# Memory.net
KiCad netlist of a schematic drawn in Altium Designer
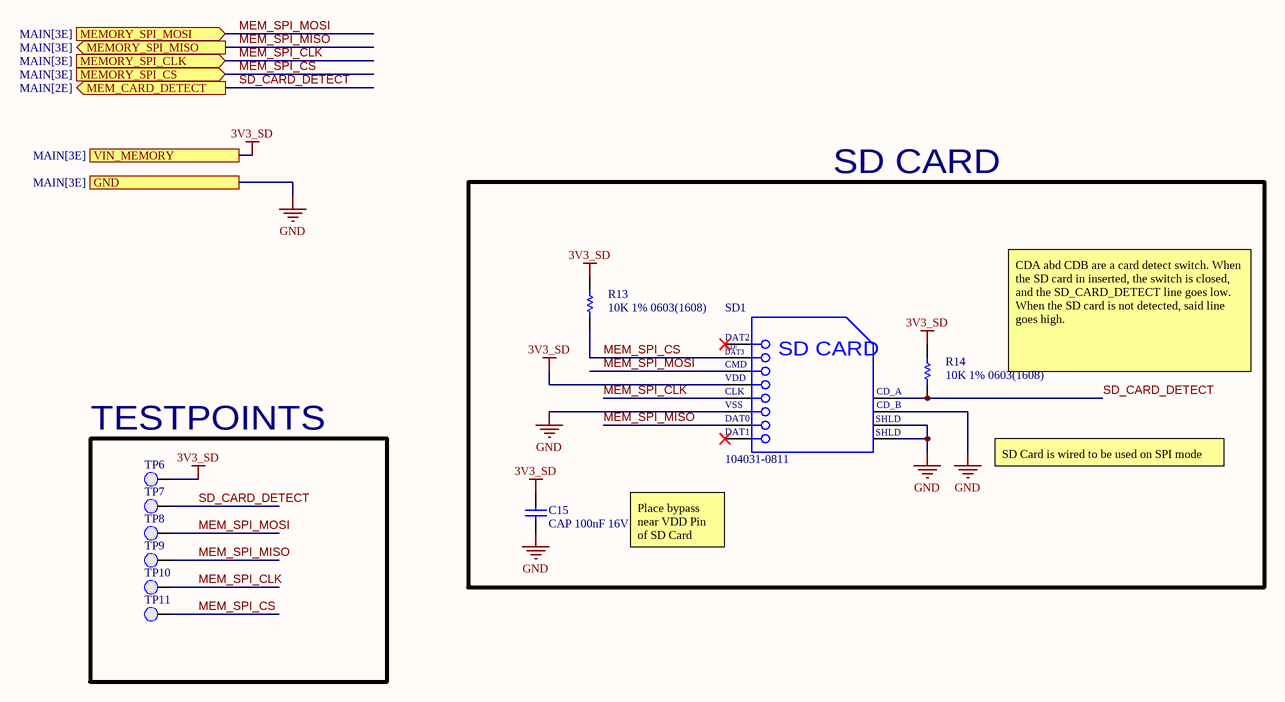
[diagram p0: Memory.SchDoc]

(export (version "E")
  (design (tool "Eeschema 10.0.6"))
  (components
    (comp (ref "C15")
      (value "CAP 100nF 16V 0603(1608)")
      (footprint "CAPC1608X95X40NL15T15")
      (fields (field (name "MANUFACTURER") "Vitramon") (field (name "PART NUMBER") "VJ0603Y104KXJCW1BC"))
      (libsource (lib "Altium Content Vault") (part "CAP"))
    )
    (comp (ref "R13")
      (value "10K 1% 0603(1608)")
      (footprint "RESC1609X55X30LL15T15")
      (description "Chip Resistor, 10 KOhm, +/- 1%, 0.1 W, -55 to 155 degC, 0603 (1608 Metric), RoHS, Tape and Reel")
      (fields (field (name "TOLERANCE") "1%") (field (name "MANUFACTURER") "Panasonic"))
      (libsource (lib "Altium Content Vault") (part "RES-2"))
    )
    (comp (ref "R14")
      (value "10K 1% 0603(1608)")
      (footprint "RESC1609X55X30LL15T15")
      (description "Chip Resistor, 10 KOhm, +/- 1%, 0.1 W, -55 to 155 degC, 0603 (1608 Metric), RoHS, Tape and Reel")
      (fields (field (name "TOLERANCE") "1%") (field (name "MANUFACTURER") "Panasonic"))
      (libsource (lib "Altium Content Vault") (part "RES-2"))
    )
    (comp (ref "SD1")
      (value "104031-0811")
      (footprint "MOLX-104031-0811_V")
      (description "Micro SD Card, RA, -25 to 85 degC, 8-Pin SMD, RoHS, Tape and Reel")
      (fields (field (name "MANUFACTURER") "Molex"))
      (libsource (lib "Altium Content Vault") (part "CN-SD-8-2SW-2S"))
    )
    (comp (ref "TP6")
      (value "0.1\" Pad")
      (footprint "PCBComponent")
      (libsource (lib "Schematics") (part "0.1{dblquote} Pad-A.4"))
    )
    (comp (ref "TP7")
      (value "0.1\" Pad")
      (footprint "PCBComponent")
      (libsource (lib "Schematics") (part "0.1{dblquote} Pad-A.4"))
    )
    (comp (ref "TP8")
      (value "0.1\" Pad")
      (footprint "PCBComponent")
      (libsource (lib "Schematics") (part "0.1{dblquote} Pad-A.4"))
    )
    (comp (ref "TP9")
      (value "0.1\" Pad")
      (footprint "PCBComponent")
      (libsource (lib "Schematics") (part "0.1{dblquote} Pad-A.4"))
    )
    (comp (ref "TP10")
      (value "0.1\" Pad")
      (footprint "PCBComponent")
      (libsource (lib "Schematics") (part "0.1{dblquote} Pad-A.4"))
    )
    (comp (ref "TP11")
      (value "0.1\" Pad")
      (footprint "PCBComponent")
      (libsource (lib "Schematics") (part "0.1{dblquote} Pad-A.4"))
    )
  )
  (nets
    (net (code "1") (name "/MEM_SPI_CLK") (class "Default")
      (node (ref "SD1") (pin "5") (pinfunction "CLK_5") (pintype "passive"))
      (node (ref "TP10") (pin "1") (pinfunction "PAD_1") (pintype "passive"))
    )
    (net (code "2") (name "/MEM_SPI_CS") (class "Default")
      (node (ref "R13") (pin "1") (pinfunction "1_1") (pintype "passive"))
      (node (ref "SD1") (pin "2") (pinfunction "CMD_2") (pintype "passive"))
      (node (ref "TP11") (pin "1") (pinfunction "PAD_1") (pintype "passive"))
    )
    (net (code "3") (name "/MEM_SPI_MISO") (class "Default")
      (node (ref "SD1") (pin "7") (pinfunction "DAT0_7") (pintype "passive"))
      (node (ref "TP9") (pin "1") (pinfunction "PAD_1") (pintype "passive"))
    )
    (net (code "4") (name "/MEM_SPI_MOSI") (class "Default")
      (node (ref "SD1") (pin "3") (pinfunction "VSS1_3") (pintype "passive"))
      (node (ref "TP8") (pin "1") (pinfunction "PAD_1") (pintype "passive"))
    )
    (net (code "5") (name "/SD_CARD_DETECT") (class "Default")
      (node (ref "R14") (pin "1") (pinfunction "1_1") (pintype "passive"))
      (node (ref "SD1") (pin "9") (pinfunction "CD_A_9") (pintype "passive"))
      (node (ref "TP7") (pin "1") (pinfunction "PAD_1") (pintype "passive"))
    )
    (net (code "6") (name "3V3_SD") (class "Default")
      (node (ref "C15") (pin "2") (pinfunction "2_2") (pintype "passive"))
      (node (ref "R13") (pin "2") (pinfunction "2_2") (pintype "passive"))
      (node (ref "R14") (pin "2") (pinfunction "2_2") (pintype "passive"))
      (node (ref "SD1") (pin "4") (pinfunction "VDD_4") (pintype "passive"))
      (node (ref "TP6") (pin "1") (pinfunction "PAD_1") (pintype "passive"))
    )
    (net (code "7") (name "GND") (class "Default")
      (node (ref "C15") (pin "1") (pinfunction "1_1") (pintype "passive"))
      (node (ref "SD1") (pin "10") (pinfunction "CD_B_10") (pintype "passive"))
      (node (ref "SD1") (pin "11") (pinfunction "SHLD1_11") (pintype "passive"))
      (node (ref "SD1") (pin "12") (pinfunction "SHLD2_12") (pintype "passive"))
      (node (ref "SD1") (pin "6") (pinfunction "VSS2_6") (pintype "passive"))
    )
    (net (code "8") (name "unconnected-(SD1-CD{slash}DAT3-Pad1)") (class "Default")
      (node (ref "SD1") (pin "1") (pinfunction "CD/DAT3_1") (pintype "passive+no_connect"))
    )
    (net (code "9") (name "unconnected-(SD1-DAT1-Pad8)") (class "Default")
      (node (ref "SD1") (pin "8") (pinfunction "DAT1_8") (pintype "passive+no_connect"))
    )
  )
)
